# ToneReal_Adapter.net
KiCad netlist of a schematic drawn in Altium Designer
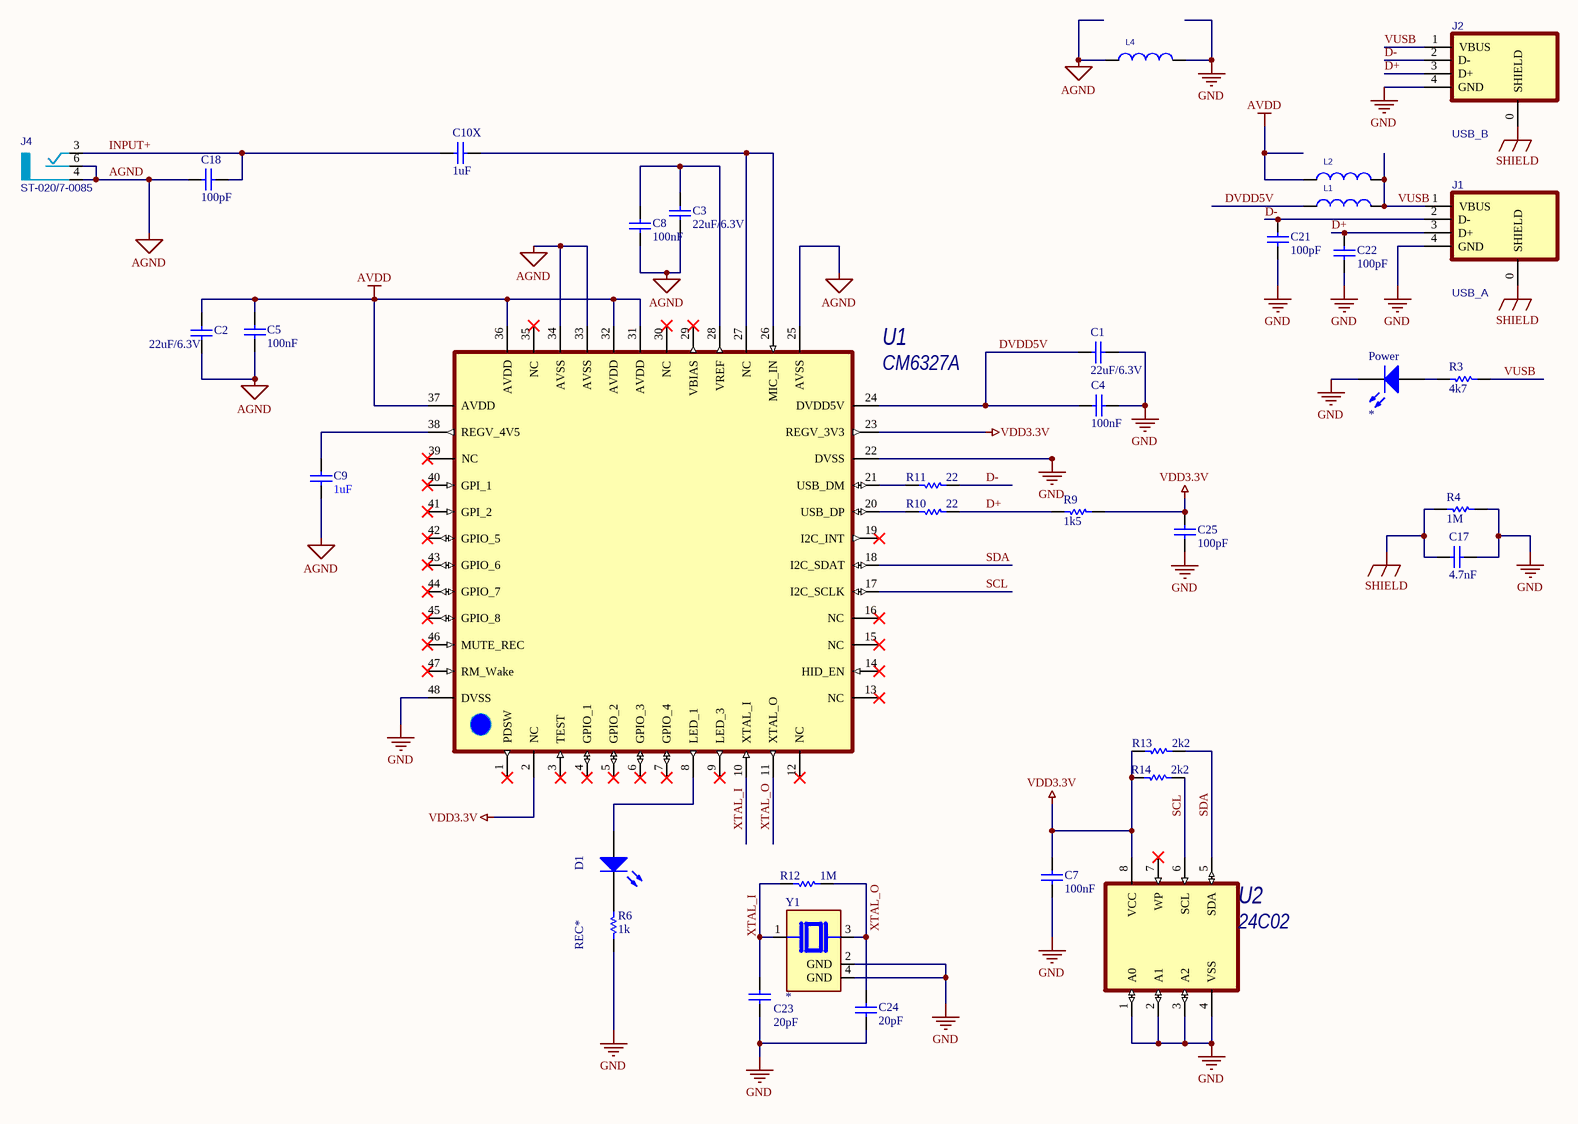
[diagram p0: ToneReal_Adapter.SchDoc]

(export (version "E")
  (design (tool "Eeschema 10.0.6"))
  (components
    (comp (ref "C1")
      (value "22uF/6.3V")
      (footprint "CERCAP SMD0805 (IPC-2012)")
      (description "Capacitor (Semiconductor SIM Model)")
      (fields (field (name "PUBLISHER") "Altium Limited"))
      (libsource (lib "Miscellaneous Devices") (part "Cap Semi"))
    )
    (comp (ref "C2")
      (value "22uF/6.3V")
      (footprint "CERCAP SMD0805 (IPC-2012)")
      (description "Capacitor (Semiconductor SIM Model)")
      (fields (field (name "PUBLISHER") "Altium Limited"))
      (libsource (lib "Miscellaneous Devices") (part "Cap Semi"))
    )
    (comp (ref "C3")
      (value "22uF/6.3V")
      (footprint "CERCAP SMD0805 (IPC-2012)")
      (description "Capacitor (Semiconductor SIM Model)")
      (fields (field (name "PUBLISHER") "Altium Limited"))
      (libsource (lib "Miscellaneous Devices") (part "Cap Semi"))
    )
    (comp (ref "C4")
      (value "100nF")
      (footprint "CERCAP SMD0603L (IPC1608L)")
      (description "Capacitor (Semiconductor SIM Model)")
      (fields (field (name "PUBLISHER") "Altium Limited"))
      (libsource (lib "Miscellaneous Devices") (part "Cap Semi"))
    )
    (comp (ref "C5")
      (value "100nF")
      (footprint "CERCAP SMD0603L (IPC1608L)")
      (description "Capacitor (Semiconductor SIM Model)")
      (fields (field (name "PUBLISHER") "Altium Limited"))
      (libsource (lib "Miscellaneous Devices") (part "Cap Semi"))
    )
    (comp (ref "C7")
      (value "100nF")
      (footprint "CERCAP SMD0603L (IPC1608L)")
      (description "Capacitor (Semiconductor SIM Model)")
      (fields (field (name "PUBLISHER") "Altium Limited"))
      (libsource (lib "Miscellaneous Devices") (part "Cap Semi"))
    )
    (comp (ref "C8")
      (value "100nF")
      (footprint "CERCAP SMD0603L (IPC1608L)")
      (description "Capacitor (Semiconductor SIM Model)")
      (fields (field (name "PUBLISHER") "Altium Limited"))
      (libsource (lib "Miscellaneous Devices") (part "Cap Semi"))
    )
    (comp (ref "C9")
      (value "1uF")
      (footprint "CERCAP SMD0603L (IPC1608L)")
      (description "Capacitor (Semiconductor SIM Model)")
      (fields (field (name "PUBLISHER") "Altium Limited"))
      (libsource (lib "Miscellaneous Devices") (part "Cap Semi"))
    )
    (comp (ref "C10X")
      (value "1uF")
      (footprint "CERCAP SMD0805 (IPC-2012)")
      (description "Capacitor (Semiconductor SIM Model)")
      (fields (field (name "PUBLISHER") "Altium Limited"))
      (libsource (lib "Miscellaneous Devices") (part "Cap Semi"))
    )
    (comp (ref "C17")
      (value "4.7nF")
      (footprint "CERCAP SMD0603L (IPC1608L)")
      (description "Capacitor (Semiconductor SIM Model)")
      (fields (field (name "PUBLISHER") "Altium Limited"))
      (libsource (lib "Miscellaneous Devices") (part "Cap Semi"))
    )
    (comp (ref "C18")
      (value "100pF")
      (footprint "CERCAP SMD0603L (IPC1608L)")
      (description "Capacitor (Semiconductor SIM Model)")
      (fields (field (name "PUBLISHER") "Altium Limited"))
      (libsource (lib "Miscellaneous Devices") (part "Cap Semi"))
    )
    (comp (ref "C21")
      (value "100pF")
      (footprint "CERCAP SMD0603L (IPC1608L)")
      (description "Capacitor (Semiconductor SIM Model)")
      (fields (field (name "PUBLISHER") "Altium Limited"))
      (libsource (lib "Miscellaneous Devices") (part "Cap Semi"))
    )
    (comp (ref "C22")
      (value "100pF")
      (footprint "CERCAP SMD0603L (IPC1608L)")
      (description "Capacitor (Semiconductor SIM Model)")
      (fields (field (name "PUBLISHER") "Altium Limited"))
      (libsource (lib "Miscellaneous Devices") (part "Cap Semi"))
    )
    (comp (ref "C23")
      (value "20pF")
      (footprint "CERCAP SMD0603L (IPC1608L)")
      (description "Capacitor (Semiconductor SIM Model)")
      (fields (field (name "PUBLISHER") "Altium Limited"))
      (libsource (lib "Miscellaneous Devices") (part "Cap Semi"))
    )
    (comp (ref "C24")
      (value "20pF")
      (footprint "CERCAP SMD0603L (IPC1608L)")
      (description "Capacitor (Semiconductor SIM Model)")
      (fields (field (name "PUBLISHER") "Altium Limited"))
      (libsource (lib "Miscellaneous Devices") (part "Cap Semi"))
    )
    (comp (ref "C25")
      (value "100pF")
      (footprint "CERCAP SMD0603L (IPC1608L)")
      (description "Capacitor (Semiconductor SIM Model)")
      (fields (field (name "PUBLISHER") "Altium Limited"))
      (libsource (lib "Miscellaneous Devices") (part "Cap Semi"))
    )
    (comp (ref "D1")
      (value "REC*")
      (footprint "SMDLED_0805")
      (description "Typical INFRARED GaAs LED")
      (fields (field (name "PUBLISHER") "Altium Limited"))
      (libsource (lib "Miscellaneous Devices") (part "LED0"))
    )
    (comp (ref "J1")
      (value "USB_A")
      (footprint "ToneReal_Adapter_v1.0:USBA_1PLAG_NO_3D")
      (fields
        (field (name "BOM_SUPPLIER PART") "C498173")
        (field (name "BOM_MANUFACTURER PART") "USB-B01")
        (field (name "CONTRIBUTOR") "LCSC")
      )
      (libsource (lib "ToneReal") (part "USB"))
    )
    (comp (ref "J2")
      (value "USB_B")
      (footprint "USB-B")
      (fields
        (field (name "BOM_SUPPLIER PART") "C498173")
        (field (name "BOM_MANUFACTURER PART") "USB-B01")
        (field (name "CONTRIBUTOR") "LCSC")
      )
      (libsource (lib "ToneReal") (part "USB"))
    )
    (comp (ref "J4")
      (value "ST-020/7-0085")
      (footprint "JACK6.3 - duplicate")
      (description "JACK6.3_MONO_R")
      (libsource (lib "ToneReal") (part "JACK6.3_MONO_R"))
    )
    (comp (ref "L1")
      (value "BLM21PG221SN1")
      (footprint "BLM18P (0603L SIZE)")
      (libsource (lib "*") (part "INDUCT"))
    )
    (comp (ref "L2")
      (value "BLM21PG221SN1")
      (footprint "BLM18P (0603L SIZE)")
      (libsource (lib "*") (part "INDUCT"))
    )
    (comp (ref "L4")
      (value "BLM21PG221SN1")
      (footprint "BLM18P (0603L SIZE)")
      (libsource (lib "*") (part "INDUCT"))
    )
    (comp (ref "Power")
      (value "*")
      (footprint "SMDLED_0805")
      (description "Typical INFRARED GaAs LED")
      (fields (field (name "PUBLISHER") "Altium Limited"))
      (libsource (lib "Miscellaneous Devices") (part "LED0"))
    )
    (comp (ref "R3")
      (value "4k7")
      (footprint "RES smd0603 (IPC-1608)")
      (description "Resistor")
      (fields (field (name "PUBLISHER") "Altium Limited"))
      (libsource (lib "Discret") (part "RES"))
    )
    (comp (ref "R4")
      (value "1M")
      (footprint "RES smd0603 (IPC-1608)")
      (description "Resistor")
      (fields (field (name "PUBLISHER") "Altium Limited"))
      (libsource (lib "Discret") (part "RES"))
    )
    (comp (ref "R6")
      (value "1k")
      (footprint "RES smd0603 (IPC-1608)")
      (description "Resistor")
      (fields (field (name "PUBLISHER") "Altium Limited"))
      (libsource (lib "") (part "RES_1"))
    )
    (comp (ref "R9")
      (value "1k5")
      (footprint "RES smd0603 (IPC-1608)")
      (description "Resistor")
      (fields (field (name "PUBLISHER") "Altium Limited"))
      (libsource (lib "Discret") (part "RES"))
    )
    (comp (ref "R10")
      (value "22")
      (footprint "RES smd0603 (IPC-1608)")
      (description "Resistor")
      (fields (field (name "PUBLISHER") "Altium Limited"))
      (libsource (lib "Discret") (part "RES"))
    )
    (comp (ref "R11")
      (value "22")
      (footprint "RES smd0603 (IPC-1608)")
      (description "Resistor")
      (fields (field (name "PUBLISHER") "Altium Limited"))
      (libsource (lib "Discret") (part "RES"))
    )
    (comp (ref "R12")
      (value "1M")
      (footprint "RES smd0603 (IPC-1608)")
      (description "Resistor")
      (fields (field (name "PUBLISHER") "Altium Limited"))
      (libsource (lib "Discret") (part "RES"))
    )
    (comp (ref "R13")
      (value "2k2")
      (footprint "RES smd0603 (IPC-1608)")
      (description "Resistor")
      (fields (field (name "PUBLISHER") "Altium Limited"))
      (libsource (lib "Discret") (part "RES"))
    )
    (comp (ref "R14")
      (value "2k2")
      (footprint "RES smd0603 (IPC-1608)")
      (description "Resistor")
      (fields (field (name "PUBLISHER") "Altium Limited"))
      (libsource (lib "Discret") (part "RES"))
    )
    (comp (ref "U1")
      (value "CM6327A")
      (footprint "QFP50P900X900X160-48N")
      (description "CM6327")
      (libsource (lib "ToneReal") (part "CM6327_1"))
    )
    (comp (ref "U2") (value "24C02") (footprint "SOIC-8") (libsource (lib "ToneReal") (part "24C02")))
    (comp (ref "Y1")
      (value "*")
      (footprint "XTAL_3225")
      (description "3225")
      (libsource (lib "ToneReal") (part "TSX-3225"))
    )
  )
  (nets
    (net (code "1") (name "/D+") (class "Default")
      (node (ref "C22") (pin "2") (pinfunction "2_2") (pintype "passive"))
      (node (ref "J1") (pin "3") (pinfunction "D+_3") (pintype "passive"))
      (node (ref "J2") (pin "3") (pinfunction "D+_3") (pintype "passive"))
      (node (ref "R10") (pin "2") (pinfunction "2_2") (pintype "passive"))
      (node (ref "R9") (pin "2") (pinfunction "2_2") (pintype "passive"))
    )
    (net (code "2") (name "/D-") (class "Default")
      (node (ref "C21") (pin "2") (pinfunction "2_2") (pintype "passive"))
      (node (ref "J1") (pin "2") (pinfunction "D-_2") (pintype "passive"))
      (node (ref "J2") (pin "2") (pinfunction "D-_2") (pintype "passive"))
      (node (ref "R11") (pin "2") (pinfunction "2_2") (pintype "passive"))
    )
    (net (code "3") (name "/DVDD5V") (class "Default")
      (node (ref "C1") (pin "2") (pinfunction "2_2") (pintype "passive"))
      (node (ref "C4") (pin "2") (pinfunction "2_2") (pintype "passive"))
      (node (ref "L1") (pin "1") (pinfunction "1_1") (pintype "passive"))
      (node (ref "U1") (pin "24") (pinfunction "DVDD5V_24") (pintype "power_in"))
    )
    (net (code "4") (name "/INPUT+") (class "Default")
      (node (ref "C10X") (pin "1") (pinfunction "1_1") (pintype "passive"))
      (node (ref "C18") (pin "1") (pinfunction "1_1") (pintype "passive"))
      (node (ref "J4") (pin "3") (pinfunction "R_CH_3") (pintype "passive"))
    )
    (net (code "5") (name "/SCL") (class "Default")
      (node (ref "R14") (pin "2") (pinfunction "2_2") (pintype "passive"))
      (node (ref "U1") (pin "17") (pinfunction "I2C_SCLK_17") (pintype "bidirectional"))
      (node (ref "U2") (pin "6") (pinfunction "SCL_6") (pintype "input"))
    )
    (net (code "6") (name "/SDA") (class "Default")
      (node (ref "R13") (pin "2") (pinfunction "2_2") (pintype "passive"))
      (node (ref "U1") (pin "18") (pinfunction "I2C_SDAT_18") (pintype "bidirectional"))
      (node (ref "U2") (pin "5") (pinfunction "SDA_5") (pintype "bidirectional"))
    )
    (net (code "7") (name "/VUSB") (class "Default")
      (node (ref "J1") (pin "1") (pinfunction "VBUS_1") (pintype "passive"))
      (node (ref "J2") (pin "1") (pinfunction "VBUS_1") (pintype "passive"))
      (node (ref "L1") (pin "2") (pinfunction "2_2") (pintype "passive"))
      (node (ref "L2") (pin "2") (pinfunction "2_2") (pintype "passive"))
      (node (ref "R3") (pin "1") (pinfunction "1_1") (pintype "passive"))
    )
    (net (code "8") (name "/XTAL_I") (class "Default")
      (node (ref "C23") (pin "2") (pinfunction "2_2") (pintype "passive"))
      (node (ref "R12") (pin "1") (pinfunction "1_1") (pintype "passive"))
      (node (ref "U1") (pin "10") (pinfunction "XTAL_I_10") (pintype "input"))
      (node (ref "Y1") (pin "1") (pinfunction "1_1") (pintype "passive"))
    )
    (net (code "9") (name "/XTAL_O") (class "Default")
      (node (ref "C24") (pin "2") (pinfunction "2_2") (pintype "passive"))
      (node (ref "R12") (pin "2") (pinfunction "2_2") (pintype "passive"))
      (node (ref "U1") (pin "11") (pinfunction "XTAL_O_11") (pintype "output"))
      (node (ref "Y1") (pin "3") (pinfunction "2_3") (pintype "passive"))
    )
    (net (code "10") (name "AGND") (class "Default")
      (node (ref "C18") (pin "2") (pinfunction "2_2") (pintype "passive"))
      (node (ref "C2") (pin "2") (pinfunction "2_2") (pintype "passive"))
      (node (ref "C3") (pin "2") (pinfunction "2_2") (pintype "passive"))
      (node (ref "C5") (pin "2") (pinfunction "2_2") (pintype "passive"))
      (node (ref "C8") (pin "2") (pinfunction "2_2") (pintype "passive"))
      (node (ref "C9") (pin "2") (pinfunction "2_2") (pintype "passive"))
      (node (ref "J4") (pin "4") (pinfunction "GND_4") (pintype "passive"))
      (node (ref "J4") (pin "6") (pinfunction "R_ch_closed_6") (pintype "passive"))
      (node (ref "L4") (pin "1") (pinfunction "1_1") (pintype "passive"))
      (node (ref "U1") (pin "25") (pinfunction "AVSS_25") (pintype "power_in"))
      (node (ref "U1") (pin "33") (pinfunction "AVSS_33") (pintype "power_in"))
      (node (ref "U1") (pin "34") (pinfunction "AVSS_34") (pintype "power_in"))
    )
    (net (code "11") (name "AVDD") (class "Default")
      (node (ref "C2") (pin "1") (pinfunction "1_1") (pintype "passive"))
      (node (ref "C5") (pin "1") (pinfunction "1_1") (pintype "passive"))
      (node (ref "L2") (pin "1") (pinfunction "1_1") (pintype "passive"))
      (node (ref "U1") (pin "31") (pinfunction "AVDD_31") (pintype "power_in"))
      (node (ref "U1") (pin "32") (pinfunction "AVDD_32") (pintype "power_in"))
      (node (ref "U1") (pin "36") (pinfunction "AVDD_36") (pintype "power_in"))
      (node (ref "U1") (pin "37") (pinfunction "AVDD_37") (pintype "power_in"))
    )
    (net (code "12") (name "GND") (class "Default")
      (node (ref "C1") (pin "1") (pinfunction "1_1") (pintype "passive"))
      (node (ref "C17") (pin "2") (pinfunction "2_2") (pintype "passive"))
      (node (ref "C21") (pin "1") (pinfunction "1_1") (pintype "passive"))
      (node (ref "C22") (pin "1") (pinfunction "1_1") (pintype "passive"))
      (node (ref "C23") (pin "1") (pinfunction "1_1") (pintype "passive"))
      (node (ref "C24") (pin "1") (pinfunction "1_1") (pintype "passive"))
      (node (ref "C25") (pin "1") (pinfunction "1_1") (pintype "passive"))
      (node (ref "C4") (pin "1") (pinfunction "1_1") (pintype "passive"))
      (node (ref "C7") (pin "1") (pinfunction "1_1") (pintype "passive"))
      (node (ref "J1") (pin "4") (pinfunction "GND_4") (pintype "passive"))
      (node (ref "J2") (pin "4") (pinfunction "GND_4") (pintype "passive"))
      (node (ref "L4") (pin "2") (pinfunction "2_2") (pintype "passive"))
      (node (ref "Power") (pin "1") (pinfunction "K_1") (pintype "passive"))
      (node (ref "R4") (pin "1") (pinfunction "1_1") (pintype "passive"))
      (node (ref "R6") (pin "2") (pinfunction "2_2") (pintype "passive"))
      (node (ref "U1") (pin "22") (pinfunction "DVSS_22") (pintype "power_in"))
      (node (ref "U1") (pin "48") (pinfunction "DVSS_48") (pintype "power_in"))
      (node (ref "U2") (pin "1") (pinfunction "A0_1") (pintype "bidirectional"))
      (node (ref "U2") (pin "2") (pinfunction "A1_2") (pintype "bidirectional"))
      (node (ref "U2") (pin "3") (pinfunction "A2_3") (pintype "bidirectional"))
      (node (ref "U2") (pin "4") (pinfunction "VSS_4") (pintype "power_in"))
      (node (ref "Y1") (pin "2") (pinfunction "GND_2") (pintype "power_in"))
      (node (ref "Y1") (pin "4") (pinfunction "GND_4") (pintype "power_in"))
    )
    (net (code "13") (name "Net-(D1-A)") (class "Default")
      (node (ref "D1") (pin "2") (pinfunction "A_2") (pintype "passive"))
      (node (ref "U1") (pin "8") (pinfunction "LED_1_8") (pintype "output"))
    )
    (net (code "14") (name "Net-(D1-K)") (class "Default")
      (node (ref "D1") (pin "1") (pinfunction "K_1") (pintype "passive"))
      (node (ref "R6") (pin "1") (pinfunction "1_1") (pintype "passive"))
    )
    (net (code "15") (name "Net-(Power-A)") (class "Default")
      (node (ref "Power") (pin "2") (pinfunction "A_2") (pintype "passive"))
      (node (ref "R3") (pin "2") (pinfunction "2_2") (pintype "passive"))
    )
    (net (code "16") (name "Net-(U1-MIC_IN)") (class "Default")
      (node (ref "C10X") (pin "2") (pinfunction "2_2") (pintype "passive"))
      (node (ref "U1") (pin "26") (pinfunction "MIC_IN_26") (pintype "input"))
      (node (ref "U1") (pin "27") (pinfunction "NC_27") (pintype "passive"))
    )
    (net (code "17") (name "Net-(U1-REGV_4V5)") (class "Default")
      (node (ref "C9") (pin "1") (pinfunction "1_1") (pintype "passive"))
      (node (ref "U1") (pin "38") (pinfunction "REGV_4V5_38") (pintype "output"))
    )
    (net (code "18") (name "Net-(U1-USB_DM)") (class "Default")
      (node (ref "R11") (pin "1") (pinfunction "1_1") (pintype "passive"))
      (node (ref "U1") (pin "21") (pinfunction "USB_DM_21") (pintype "bidirectional"))
    )
    (net (code "19") (name "Net-(U1-USB_DP)") (class "Default")
      (node (ref "R10") (pin "1") (pinfunction "1_1") (pintype "passive"))
      (node (ref "U1") (pin "20") (pinfunction "USB_DP_20") (pintype "bidirectional"))
    )
    (net (code "20") (name "Net-(U1-VREF)") (class "Default")
      (node (ref "C3") (pin "1") (pinfunction "1_1") (pintype "passive"))
      (node (ref "C8") (pin "1") (pinfunction "1_1") (pintype "passive"))
      (node (ref "U1") (pin "28") (pinfunction "VREF_28") (pintype "output"))
    )
    (net (code "21") (name "SHIELD") (class "Default")
      (node (ref "C17") (pin "1") (pinfunction "1_1") (pintype "passive"))
      (node (ref "J1") (pin "0") (pinfunction "SHIELD_0") (pintype "passive"))
      (node (ref "J2") (pin "0") (pinfunction "SHIELD_0") (pintype "passive"))
      (node (ref "R4") (pin "2") (pinfunction "2_2") (pintype "passive"))
    )
    (net (code "22") (name "VDD3.3V") (class "Default")
      (node (ref "C25") (pin "2") (pinfunction "2_2") (pintype "passive"))
      (node (ref "C7") (pin "2") (pinfunction "2_2") (pintype "passive"))
      (node (ref "R13") (pin "1") (pinfunction "1_1") (pintype "passive"))
      (node (ref "R14") (pin "1") (pinfunction "1_1") (pintype "passive"))
      (node (ref "R9") (pin "1") (pinfunction "1_1") (pintype "passive"))
      (node (ref "U1") (pin "2") (pinfunction "NC_2") (pintype "passive"))
      (node (ref "U1") (pin "23") (pinfunction "REGV_3V3_23") (pintype "output"))
      (node (ref "U2") (pin "8") (pinfunction "VCC_8") (pintype "power_in"))
    )
    (net (code "23") (name "unconnected-(U1-GPIO_1-Pad4)") (class "Default")
      (node (ref "U1") (pin "4") (pinfunction "GPIO_1_4") (pintype "bidirectional+no_connect"))
    )
    (net (code "24") (name "unconnected-(U1-GPIO_2-Pad5)") (class "Default")
      (node (ref "U1") (pin "5") (pinfunction "GPIO_2_5") (pintype "bidirectional+no_connect"))
    )
    (net (code "25") (name "unconnected-(U1-GPIO_3-Pad6)") (class "Default")
      (node (ref "U1") (pin "6") (pinfunction "GPIO_3_6") (pintype "bidirectional+no_connect"))
    )
    (net (code "26") (name "unconnected-(U1-GPIO_4-Pad7)") (class "Default")
      (node (ref "U1") (pin "7") (pinfunction "GPIO_4_7") (pintype "bidirectional+no_connect"))
    )
    (net (code "27") (name "unconnected-(U1-GPIO_5-Pad42)") (class "Default")
      (node (ref "U1") (pin "42") (pinfunction "GPIO_5_42") (pintype "bidirectional+no_connect"))
    )
    (net (code "28") (name "unconnected-(U1-GPIO_6-Pad43)") (class "Default")
      (node (ref "U1") (pin "43") (pinfunction "GPIO_6_43") (pintype "bidirectional+no_connect"))
    )
    (net (code "29") (name "unconnected-(U1-GPIO_7-Pad44)") (class "Default")
      (node (ref "U1") (pin "44") (pinfunction "GPIO_7_44") (pintype "bidirectional+no_connect"))
    )
    (net (code "30") (name "unconnected-(U1-GPIO_8-Pad45)") (class "Default")
      (node (ref "U1") (pin "45") (pinfunction "GPIO_8_45") (pintype "bidirectional+no_connect"))
    )
    (net (code "31") (name "unconnected-(U1-GPI_1-Pad40)") (class "Default")
      (node (ref "U1") (pin "40") (pinfunction "GPI_1_40") (pintype "input+no_connect"))
    )
    (net (code "32") (name "unconnected-(U1-GPI_2-Pad41)") (class "Default")
      (node (ref "U1") (pin "41") (pinfunction "GPI_2_41") (pintype "input+no_connect"))
    )
    (net (code "33") (name "unconnected-(U1-HID_EN-Pad14)") (class "Default")
      (node (ref "U1") (pin "14") (pinfunction "HID_EN_14") (pintype "input+no_connect"))
    )
    (net (code "34") (name "unconnected-(U1-I2C_INT-Pad19)") (class "Default")
      (node (ref "U1") (pin "19") (pinfunction "I2C_INT_19") (pintype "output+no_connect"))
    )
    (net (code "35") (name "unconnected-(U1-LED_3-Pad9)") (class "Default")
      (node (ref "U1") (pin "9") (pinfunction "LED_3_9") (pintype "output+no_connect"))
    )
    (net (code "36") (name "unconnected-(U1-MUTE_REC-Pad46)") (class "Default")
      (node (ref "U1") (pin "46") (pinfunction "MUTE_REC_46") (pintype "input+no_connect"))
    )
    (net (code "37") (name "unconnected-(U1-NC-Pad12)") (class "Default")
      (node (ref "U1") (pin "12") (pinfunction "NC_12") (pintype "passive+no_connect"))
    )
    (net (code "38") (name "unconnected-(U1-NC-Pad13)") (class "Default")
      (node (ref "U1") (pin "13") (pinfunction "NC_13") (pintype "passive+no_connect"))
    )
    (net (code "39") (name "unconnected-(U1-NC-Pad15)") (class "Default")
      (node (ref "U1") (pin "15") (pinfunction "NC_15") (pintype "passive+no_connect"))
    )
    (net (code "40") (name "unconnected-(U1-NC-Pad16)") (class "Default")
      (node (ref "U1") (pin "16") (pinfunction "NC_16") (pintype "passive+no_connect"))
    )
    (net (code "41") (name "unconnected-(U1-NC-Pad30)") (class "Default")
      (node (ref "U1") (pin "30") (pinfunction "NC_30") (pintype "passive+no_connect"))
    )
    (net (code "42") (name "unconnected-(U1-NC-Pad35)") (class "Default")
      (node (ref "U1") (pin "35") (pinfunction "NC_35") (pintype "passive+no_connect"))
    )
    (net (code "43") (name "unconnected-(U1-NC-Pad39)") (class "Default")
      (node (ref "U1") (pin "39") (pinfunction "NC_39") (pintype "passive+no_connect"))
    )
    (net (code "44") (name "unconnected-(U1-PDSW-Pad1)") (class "Default")
      (node (ref "U1") (pin "1") (pinfunction "PDSW_1") (pintype "output+no_connect"))
    )
    (net (code "45") (name "unconnected-(U1-RM_Wake-Pad47)") (class "Default")
      (node (ref "U1") (pin "47") (pinfunction "RM_Wake_47") (pintype "input+no_connect"))
    )
    (net (code "46") (name "unconnected-(U1-TEST-Pad3)") (class "Default")
      (node (ref "U1") (pin "3") (pinfunction "TEST_3") (pintype "input+no_connect"))
    )
    (net (code "47") (name "unconnected-(U1-VBIAS-Pad29)") (class "Default")
      (node (ref "U1") (pin "29") (pinfunction "VBIAS_29") (pintype "output+no_connect"))
    )
    (net (code "48") (name "unconnected-(U2-WP-Pad7)") (class "Default")
      (node (ref "U2") (pin "7") (pinfunction "WP_7") (pintype "input+no_connect"))
    )
  )
)
